# power_mux-v13.net
KiCad netlist of a schematic drawn in EAGLE
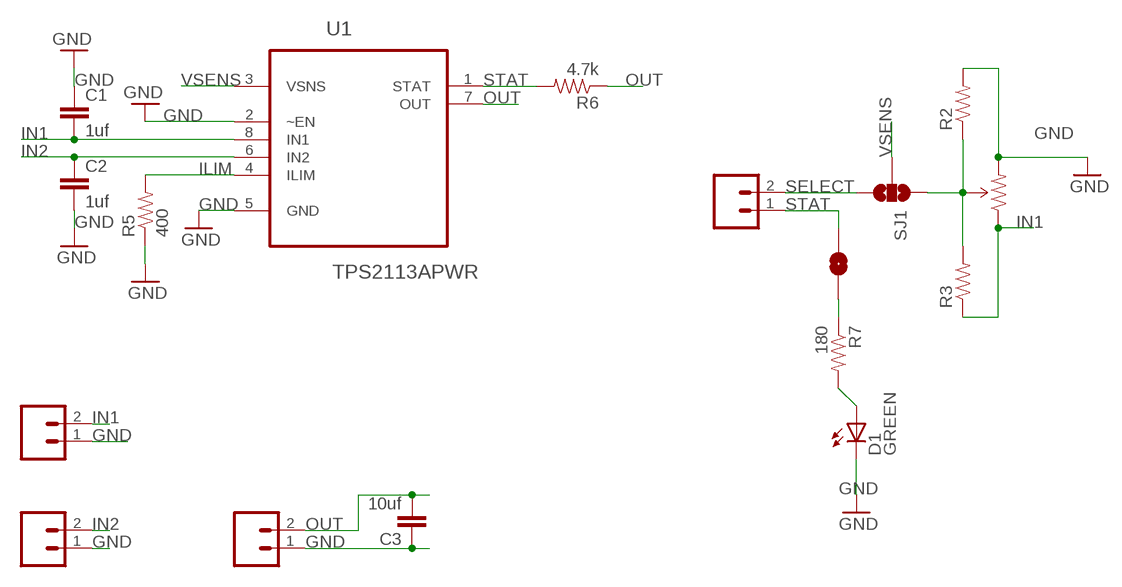
[diagram p0: schematic, sheet 1]

(export (version "E")
  (design (tool "Eeschema 10.0.6"))
  (components
    (comp (ref "C1")
      (value "1uf")
      (footprint "eagle-import:0603-CAP")
      (libsource (lib "eagle-import") (part "SparkFun-Passives_CAP0603-CAP"))
    )
    (comp (ref "C2")
      (value "1uf")
      (footprint "eagle-import:0603-CAP")
      (libsource (lib "eagle-import") (part "SparkFun-Passives_CAP0603-CAP"))
    )
    (comp (ref "C3")
      (value "10uf")
      (footprint "eagle-import:0603-CAP")
      (libsource (lib "eagle-import") (part "CAP0603-CAP"))
    )
    (comp (ref "D1")
      (value "GREEN")
      (footprint "eagle-import:LED-0603")
      (libsource (lib "eagle-import") (part "LED-GREEN0603"))
    )
    (comp (ref "JP3")
      (value "M021X02_NO_SILK")
      (footprint "eagle-import:1X02_NO_SILK")
      (libsource (lib "eagle-import") (part "M021X02_NO_SILK"))
    )
    (comp (ref "JP4")
      (value "M021X02_NO_SILK")
      (footprint "eagle-import:1X02_NO_SILK")
      (libsource (lib "eagle-import") (part "M021X02_NO_SILK"))
    )
    (comp (ref "JP5")
      (value "M021X02_NO_SILK")
      (footprint "eagle-import:1X02_NO_SILK")
      (libsource (lib "eagle-import") (part "M021X02_NO_SILK"))
    )
    (comp (ref "JP6")
      (value "M021X02_NO_SILK")
      (footprint "eagle-import:1X02_NO_SILK")
      (libsource (lib "eagle-import") (part "M021X02_NO_SILK"))
    )
    (comp (ref "R1")
      (value "TRIMPOT-PTH-KNOB")
      (footprint "eagle-import:3386U")
      (libsource (lib "eagle-import") (part "TRIMPOT-PTH-KNOB"))
    )
    (comp (ref "R2")
      (value "RESISTOR0603")
      (footprint "eagle-import:0603-RES")
      (libsource (lib "eagle-import") (part "RESISTOR0603"))
    )
    (comp (ref "R3")
      (value "RESISTOR0603")
      (footprint "eagle-import:0603-RES")
      (libsource (lib "eagle-import") (part "RESISTOR0603"))
    )
    (comp (ref "R5")
      (value "400")
      (footprint "eagle-import:0603-RES")
      (libsource (lib "eagle-import") (part "RESISTOR0603-RES"))
    )
    (comp (ref "R6")
      (value "4.7k")
      (footprint "eagle-import:0603-RES")
      (libsource (lib "eagle-import") (part "RESISTOR0603-RES"))
    )
    (comp (ref "R7")
      (value "180")
      (footprint "eagle-import:0603-RES")
      (libsource (lib "eagle-import") (part "RESISTOR0603-RES"))
    )
    (comp (ref "SJ1")
      (value "SOLDERJUMPER_2WAYPASTE1&2")
      (footprint "eagle-import:SJ_3_PASTE1&2")
      (libsource (lib "eagle-import") (part "SOLDERJUMPER_2WAYPASTE1&2"))
    )
    (comp (ref "SJ2")
      (value "SOLDERJUMPERNC2")
      (footprint "eagle-import:SJ_2S-NOTRACE")
      (libsource (lib "eagle-import") (part "SOLDERJUMPERNC2"))
    )
    (comp (ref "U1")
      (value "TPS2113APWR")
      (footprint "eagle-import:SOP65P640X120-8N")
      (libsource (lib "eagle-import") (part "TPS2113APWR"))
    )
  )
  (nets
    (net (code "1") (name "/ILIM") (class "Default")
      (node (ref "R5") (pin "2") (pinfunction "2_2") (pintype "passive"))
      (node (ref "U1") (pin "4") (pinfunction "ILIM_4") (pintype "input"))
    )
    (net (code "2") (name "/IN1") (class "Default")
      (node (ref "C1") (pin "2") (pinfunction "2_2") (pintype "passive"))
      (node (ref "JP3") (pin "2") (pinfunction "2_2") (pintype "passive"))
      (node (ref "R1") (pin "1") (pinfunction "CCW_1") (pintype "passive"))
      (node (ref "R3") (pin "1") (pinfunction "1_1") (pintype "passive"))
      (node (ref "U1") (pin "8") (pinfunction "IN1_8") (pintype "input"))
    )
    (net (code "3") (name "/IN2") (class "Default")
      (node (ref "C2") (pin "1") (pinfunction "1_1") (pintype "passive"))
      (node (ref "JP4") (pin "2") (pinfunction "2_2") (pintype "passive"))
      (node (ref "U1") (pin "6") (pinfunction "IN2_6") (pintype "input"))
    )
    (net (code "4") (name "/OUT") (class "Default")
      (node (ref "C3") (pin "2") (pinfunction "2_2") (pintype "passive"))
      (node (ref "JP6") (pin "2") (pinfunction "2_2") (pintype "passive"))
      (node (ref "R6") (pin "1") (pinfunction "1_1") (pintype "passive"))
      (node (ref "U1") (pin "7") (pinfunction "OUT_7") (pintype "output"))
    )
    (net (code "5") (name "/SELECT") (class "Default")
      (node (ref "JP5") (pin "2") (pinfunction "2_2") (pintype "passive"))
      (node (ref "SJ1") (pin "3") (pinfunction "3_3") (pintype "passive"))
    )
    (net (code "6") (name "/STAT") (class "Default")
      (node (ref "JP5") (pin "1") (pinfunction "1_1") (pintype "passive"))
      (node (ref "R6") (pin "2") (pinfunction "2_2") (pintype "passive"))
      (node (ref "SJ2") (pin "2") (pinfunction "2_2") (pintype "passive"))
      (node (ref "U1") (pin "1") (pinfunction "STAT_1") (pintype "output"))
    )
    (net (code "7") (name "/VSENS") (class "Default")
      (node (ref "SJ1") (pin "2") (pinfunction "2_2") (pintype "passive"))
      (node (ref "U1") (pin "3") (pinfunction "VSNS_3") (pintype "power_in"))
    )
    (net (code "8") (name "GND") (class "Default")
      (node (ref "C1") (pin "1") (pinfunction "1_1") (pintype "passive"))
      (node (ref "C2") (pin "2") (pinfunction "2_2") (pintype "passive"))
      (node (ref "C3") (pin "1") (pinfunction "1_1") (pintype "passive"))
      (node (ref "D1") (pin "C") (pinfunction "C_C") (pintype "passive"))
      (node (ref "JP3") (pin "1") (pinfunction "1_1") (pintype "passive"))
      (node (ref "JP4") (pin "1") (pinfunction "1_1") (pintype "passive"))
      (node (ref "JP6") (pin "1") (pinfunction "1_1") (pintype "passive"))
      (node (ref "R1") (pin "3") (pinfunction "CW_3") (pintype "passive"))
      (node (ref "R2") (pin "2") (pinfunction "2_2") (pintype "passive"))
      (node (ref "R5") (pin "1") (pinfunction "1_1") (pintype "passive"))
      (node (ref "U1") (pin "2") (pinfunction "~{EN}_2") (pintype "input"))
      (node (ref "U1") (pin "5") (pinfunction "GND_5") (pintype "passive"))
    )
    (net (code "9") (name "Net-(D1-PadA)") (class "Default")
      (node (ref "D1") (pin "A") (pinfunction "A_A") (pintype "passive"))
      (node (ref "R7") (pin "2") (pinfunction "2_2") (pintype "passive"))
    )
    (net (code "10") (name "Net-(R1-WIPER)") (class "Default")
      (node (ref "R1") (pin "2") (pinfunction "WIPER_2") (pintype "passive"))
      (node (ref "R2") (pin "1") (pinfunction "1_1") (pintype "passive"))
      (node (ref "R3") (pin "2") (pinfunction "2_2") (pintype "passive"))
      (node (ref "SJ1") (pin "1") (pinfunction "1_1") (pintype "passive"))
    )
    (net (code "11") (name "Net-(R7-Pad1)") (class "Default")
      (node (ref "R7") (pin "1") (pinfunction "1_1") (pintype "passive"))
      (node (ref "SJ2") (pin "1") (pinfunction "1_1") (pintype "passive"))
    )
  )
)
